# radiationwatch-digipot1a_small.net
KiCad netlist of a schematic drawn in EAGLE
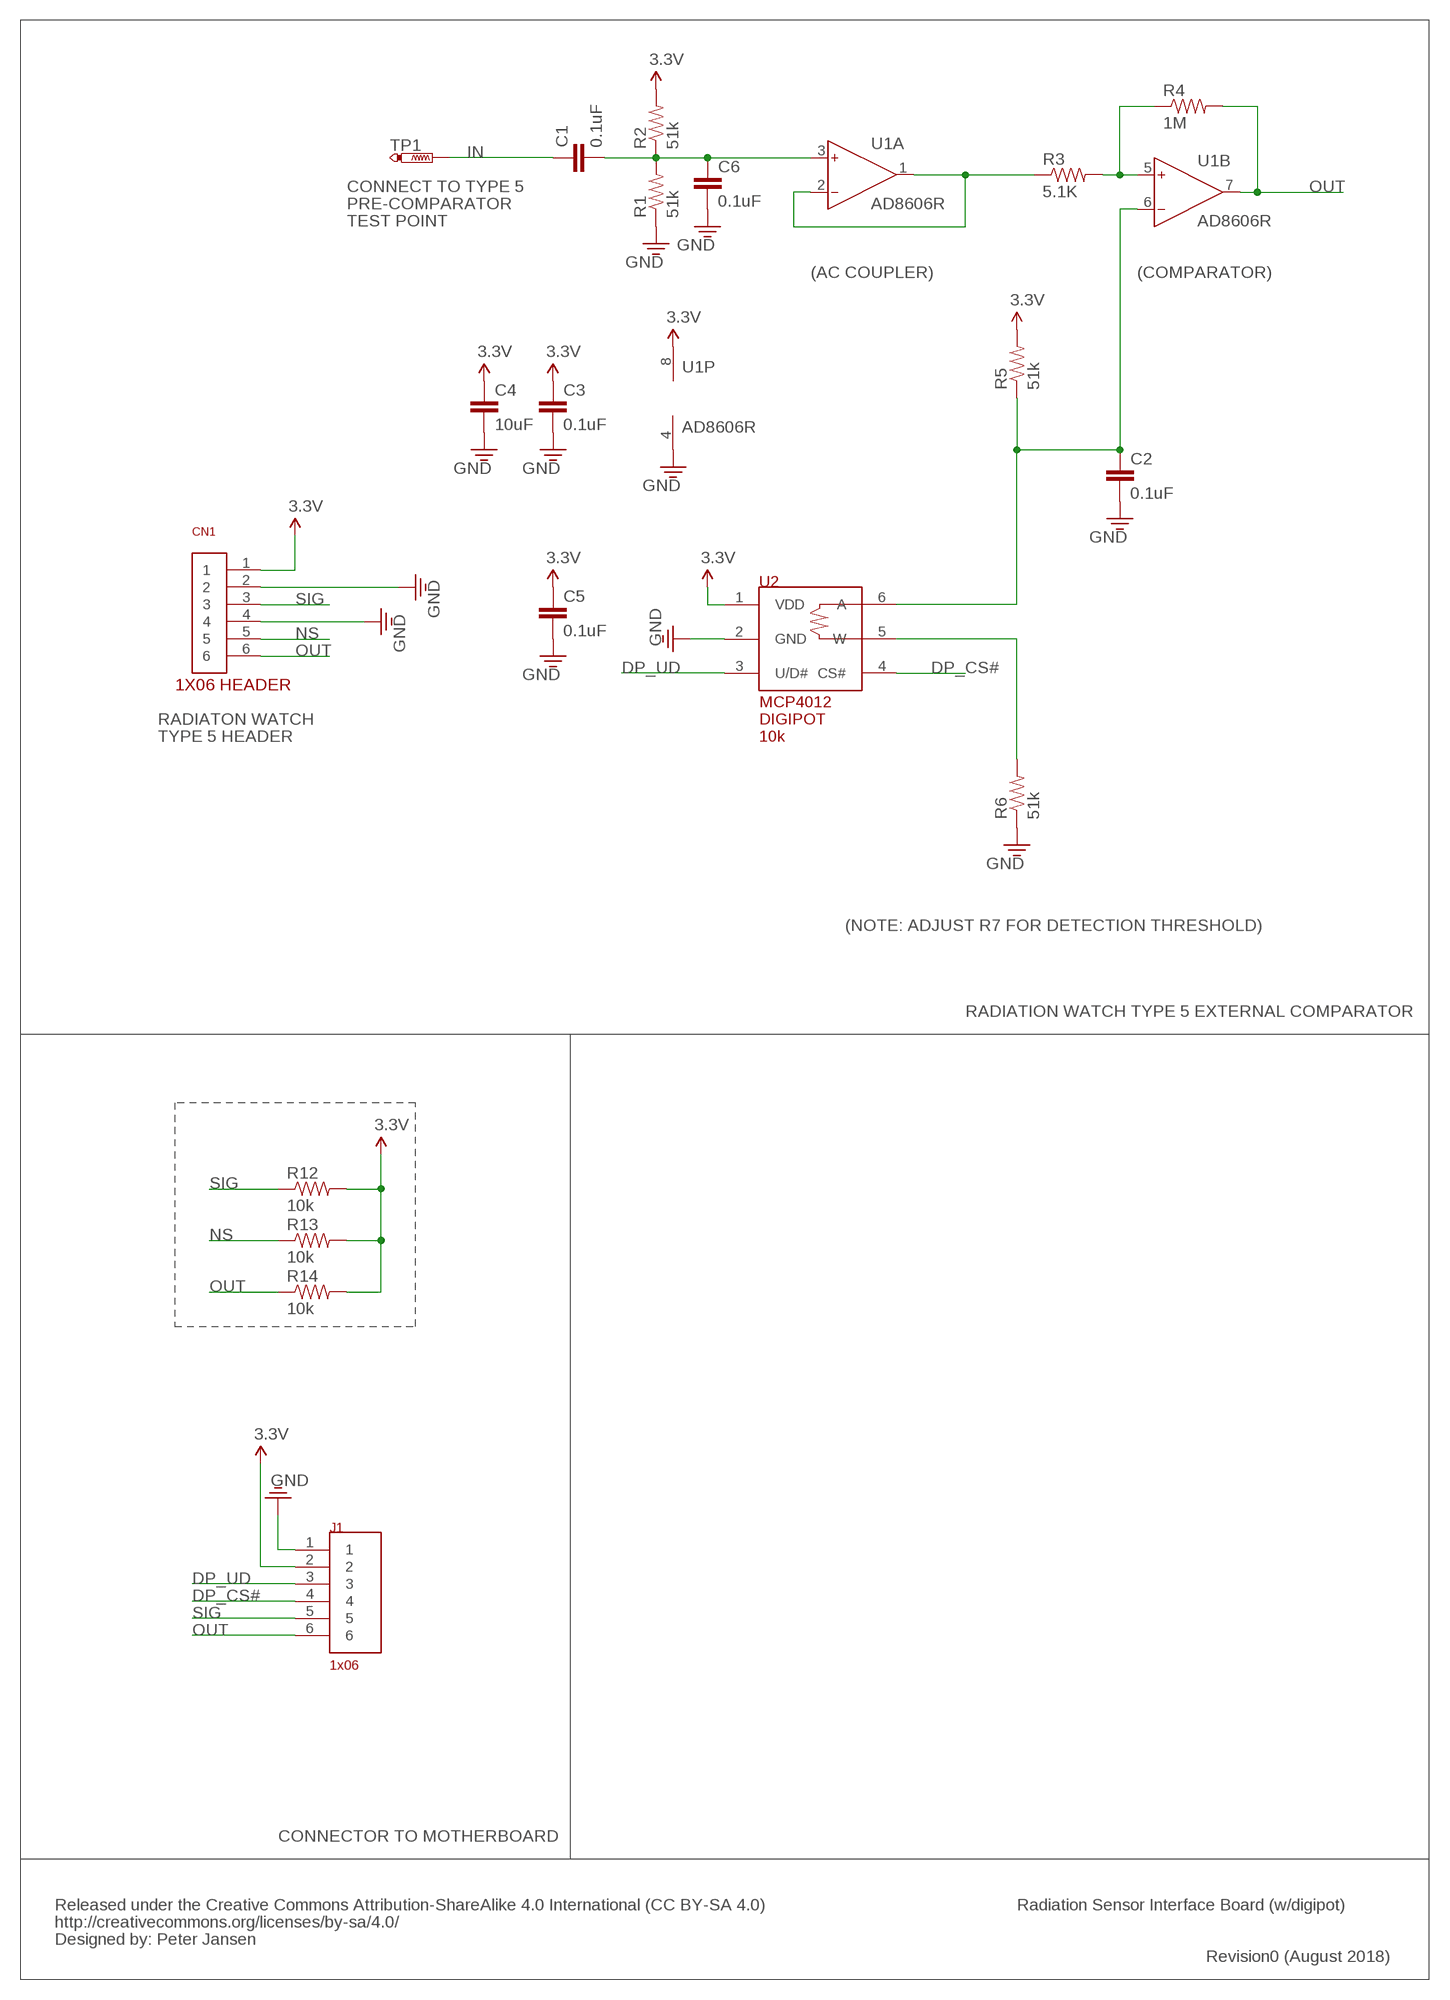
[diagram p0: schematic, sheet 1]

(export (version "E")
  (design (tool "Eeschema 10.0.6"))
  (components
    (comp (ref "C1")
      (value "0.1uF")
      (footprint "eagle-import:0603")
      (libsource (lib "eagle-import") (part "CAP0603"))
    )
    (comp (ref "C2")
      (value "0.1uF")
      (footprint "eagle-import:0603")
      (libsource (lib "eagle-import") (part "CAP0603"))
    )
    (comp (ref "C3")
      (value "0.1uF")
      (footprint "eagle-import:0603")
      (libsource (lib "eagle-import") (part "CAP0603"))
    )
    (comp (ref "C4")
      (value "10uF")
      (footprint "eagle-import:0603")
      (libsource (lib "eagle-import") (part "CAP0603"))
    )
    (comp (ref "C5")
      (value "0.1uF")
      (footprint "eagle-import:0603")
      (libsource (lib "eagle-import") (part "CAP0603"))
    )
    (comp (ref "C6")
      (value "0.1uF")
      (footprint "eagle-import:0603")
      (libsource (lib "eagle-import") (part "CAP0603"))
    )
    (comp (ref "CN1")
      (value "1X06")
      (footprint "eagle-import:1X06")
      (libsource (lib "eagle-import") (part "1X06"))
    )
    (comp (ref "J1")
      (value "1X06")
      (footprint "eagle-import:JST-SM06B-1MM")
      (libsource (lib "eagle-import") (part "notes_1X06"))
    )
    (comp (ref "R1")
      (value "51k")
      (footprint "eagle-import:0603")
      (libsource (lib "eagle-import") (part "RESISTOR0603"))
    )
    (comp (ref "R2")
      (value "51k")
      (footprint "eagle-import:0603")
      (libsource (lib "eagle-import") (part "RESISTOR0603"))
    )
    (comp (ref "R3")
      (value "5.1K")
      (footprint "eagle-import:0603")
      (libsource (lib "eagle-import") (part "RESISTOR0603"))
    )
    (comp (ref "R4")
      (value "1M")
      (footprint "eagle-import:0603")
      (libsource (lib "eagle-import") (part "RESISTOR0603"))
    )
    (comp (ref "R5")
      (value "51k")
      (footprint "eagle-import:0603")
      (libsource (lib "eagle-import") (part "RESISTOR0603"))
    )
    (comp (ref "R6")
      (value "51k")
      (footprint "eagle-import:0603")
      (libsource (lib "eagle-import") (part "RESISTOR0603"))
    )
    (comp (ref "R12")
      (value "10k")
      (footprint "eagle-import:0603")
      (libsource (lib "eagle-import") (part "RESISTOR0603"))
    )
    (comp (ref "R13")
      (value "10k")
      (footprint "eagle-import:0603")
      (libsource (lib "eagle-import") (part "RESISTOR0603"))
    )
    (comp (ref "R14")
      (value "10k")
      (footprint "eagle-import:0603")
      (libsource (lib "eagle-import") (part "RESISTOR0603"))
    )
    (comp (ref "TP1")
      (value "PTR1PAD1-13")
      (footprint "eagle-import:P1-13")
      (libsource (lib "eagle-import") (part "PTR1PAD1-13"))
    )
    (comp (ref "U1")
      (value "AD8606R")
      (footprint "eagle-import:SO8")
      (fields (field (name "MPN") "AD8607ARMZ-R2"))
      (libsource (lib "eagle-import") (part "AD8607R"))
    )
    (comp (ref "U2")
      (value "10k")
      (footprint "eagle-import:SOT-23-6")
      (libsource (lib "eagle-import") (part "MCP4012"))
    )
  )
  (nets
    (net (code "1") (name "/DP_CS#") (class "Default")
      (node (ref "J1") (pin "4") (pinfunction "4_4") (pintype "bidirectional"))
      (node (ref "U2") (pin "4") (pinfunction "CS#_4") (pintype "bidirectional"))
    )
    (net (code "2") (name "/DP_UD") (class "Default")
      (node (ref "J1") (pin "3") (pinfunction "3_3") (pintype "bidirectional"))
      (node (ref "U2") (pin "3") (pinfunction "U/D#_3") (pintype "bidirectional"))
    )
    (net (code "3") (name "/IN") (class "Default")
      (node (ref "C1") (pin "1") (pinfunction "1_1") (pintype "passive"))
      (node (ref "TP1") (pin "TP") (pinfunction "TP_TP") (pintype "input"))
    )
    (net (code "4") (name "/NS") (class "Default")
      (node (ref "CN1") (pin "5") (pinfunction "5_5") (pintype "bidirectional"))
      (node (ref "R13") (pin "1") (pinfunction "1_1") (pintype "passive"))
    )
    (net (code "5") (name "/OUT") (class "Default")
      (node (ref "CN1") (pin "6") (pinfunction "6_6") (pintype "bidirectional"))
      (node (ref "J1") (pin "6") (pinfunction "6_6") (pintype "bidirectional"))
      (node (ref "R14") (pin "1") (pinfunction "1_1") (pintype "passive"))
      (node (ref "R4") (pin "2") (pinfunction "2_2") (pintype "passive"))
      (node (ref "U1") (pin "7") (pinfunction "OUT_7") (pintype "output"))
    )
    (net (code "6") (name "/SIG") (class "Default")
      (node (ref "CN1") (pin "3") (pinfunction "3_3") (pintype "bidirectional"))
      (node (ref "J1") (pin "5") (pinfunction "5_5") (pintype "bidirectional"))
      (node (ref "R12") (pin "1") (pinfunction "1_1") (pintype "passive"))
    )
    (net (code "7") (name "3.3V") (class "Default")
      (node (ref "C3") (pin "1") (pinfunction "1_1") (pintype "passive"))
      (node (ref "C4") (pin "1") (pinfunction "1_1") (pintype "passive"))
      (node (ref "C5") (pin "1") (pinfunction "1_1") (pintype "passive"))
      (node (ref "CN1") (pin "1") (pinfunction "1_1") (pintype "bidirectional"))
      (node (ref "J1") (pin "2") (pinfunction "2_2") (pintype "bidirectional"))
      (node (ref "R12") (pin "2") (pinfunction "2_2") (pintype "passive"))
      (node (ref "R13") (pin "2") (pinfunction "2_2") (pintype "passive"))
      (node (ref "R14") (pin "2") (pinfunction "2_2") (pintype "passive"))
      (node (ref "R2") (pin "2") (pinfunction "2_2") (pintype "passive"))
      (node (ref "R5") (pin "2") (pinfunction "2_2") (pintype "passive"))
      (node (ref "U1") (pin "8") (pinfunction "V+_8") (pintype "power_in"))
      (node (ref "U2") (pin "1") (pinfunction "VDD_1") (pintype "bidirectional"))
    )
    (net (code "8") (name "GND") (class "Default")
      (node (ref "C2") (pin "2") (pinfunction "2_2") (pintype "passive"))
      (node (ref "C3") (pin "2") (pinfunction "2_2") (pintype "passive"))
      (node (ref "C4") (pin "2") (pinfunction "2_2") (pintype "passive"))
      (node (ref "C5") (pin "2") (pinfunction "2_2") (pintype "passive"))
      (node (ref "C6") (pin "2") (pinfunction "2_2") (pintype "passive"))
      (node (ref "CN1") (pin "2") (pinfunction "2_2") (pintype "bidirectional"))
      (node (ref "CN1") (pin "4") (pinfunction "4_4") (pintype "bidirectional"))
      (node (ref "J1") (pin "1") (pinfunction "1_1") (pintype "bidirectional"))
      (node (ref "R1") (pin "1") (pinfunction "1_1") (pintype "passive"))
      (node (ref "R6") (pin "1") (pinfunction "1_1") (pintype "passive"))
      (node (ref "U1") (pin "4") (pinfunction "V-_4") (pintype "power_in"))
      (node (ref "U2") (pin "2") (pinfunction "GND_2") (pintype "bidirectional"))
    )
    (net (code "9") (name "Net-(U1A-IN+)") (class "Default")
      (node (ref "C1") (pin "2") (pinfunction "2_2") (pintype "passive"))
      (node (ref "C6") (pin "1") (pinfunction "1_1") (pintype "passive"))
      (node (ref "R1") (pin "2") (pinfunction "2_2") (pintype "passive"))
      (node (ref "R2") (pin "1") (pinfunction "1_1") (pintype "passive"))
      (node (ref "U1") (pin "3") (pinfunction "IN+_3") (pintype "input"))
    )
    (net (code "10") (name "Net-(U1A-IN-)") (class "Default")
      (node (ref "R3") (pin "1") (pinfunction "1_1") (pintype "passive"))
      (node (ref "U1") (pin "1") (pinfunction "OUT_1") (pintype "output"))
      (node (ref "U1") (pin "2") (pinfunction "IN-_2") (pintype "input"))
    )
    (net (code "11") (name "Net-(U1B-IN+)") (class "Default")
      (node (ref "R3") (pin "2") (pinfunction "2_2") (pintype "passive"))
      (node (ref "R4") (pin "1") (pinfunction "1_1") (pintype "passive"))
      (node (ref "U1") (pin "5") (pinfunction "IN+_5") (pintype "input"))
    )
    (net (code "12") (name "Net-(U1B-IN-)") (class "Default")
      (node (ref "C2") (pin "1") (pinfunction "1_1") (pintype "passive"))
      (node (ref "R5") (pin "1") (pinfunction "1_1") (pintype "passive"))
      (node (ref "U1") (pin "6") (pinfunction "IN-_6") (pintype "input"))
      (node (ref "U2") (pin "6") (pinfunction "A_6") (pintype "bidirectional"))
    )
    (net (code "13") (name "Net-(U2-W)") (class "Default")
      (node (ref "R6") (pin "2") (pinfunction "2_2") (pintype "passive"))
      (node (ref "U2") (pin "5") (pinfunction "W_5") (pintype "bidirectional"))
    )
  )
)
